# kegboard-mini.net
KiCad netlist of a schematic drawn in EAGLE
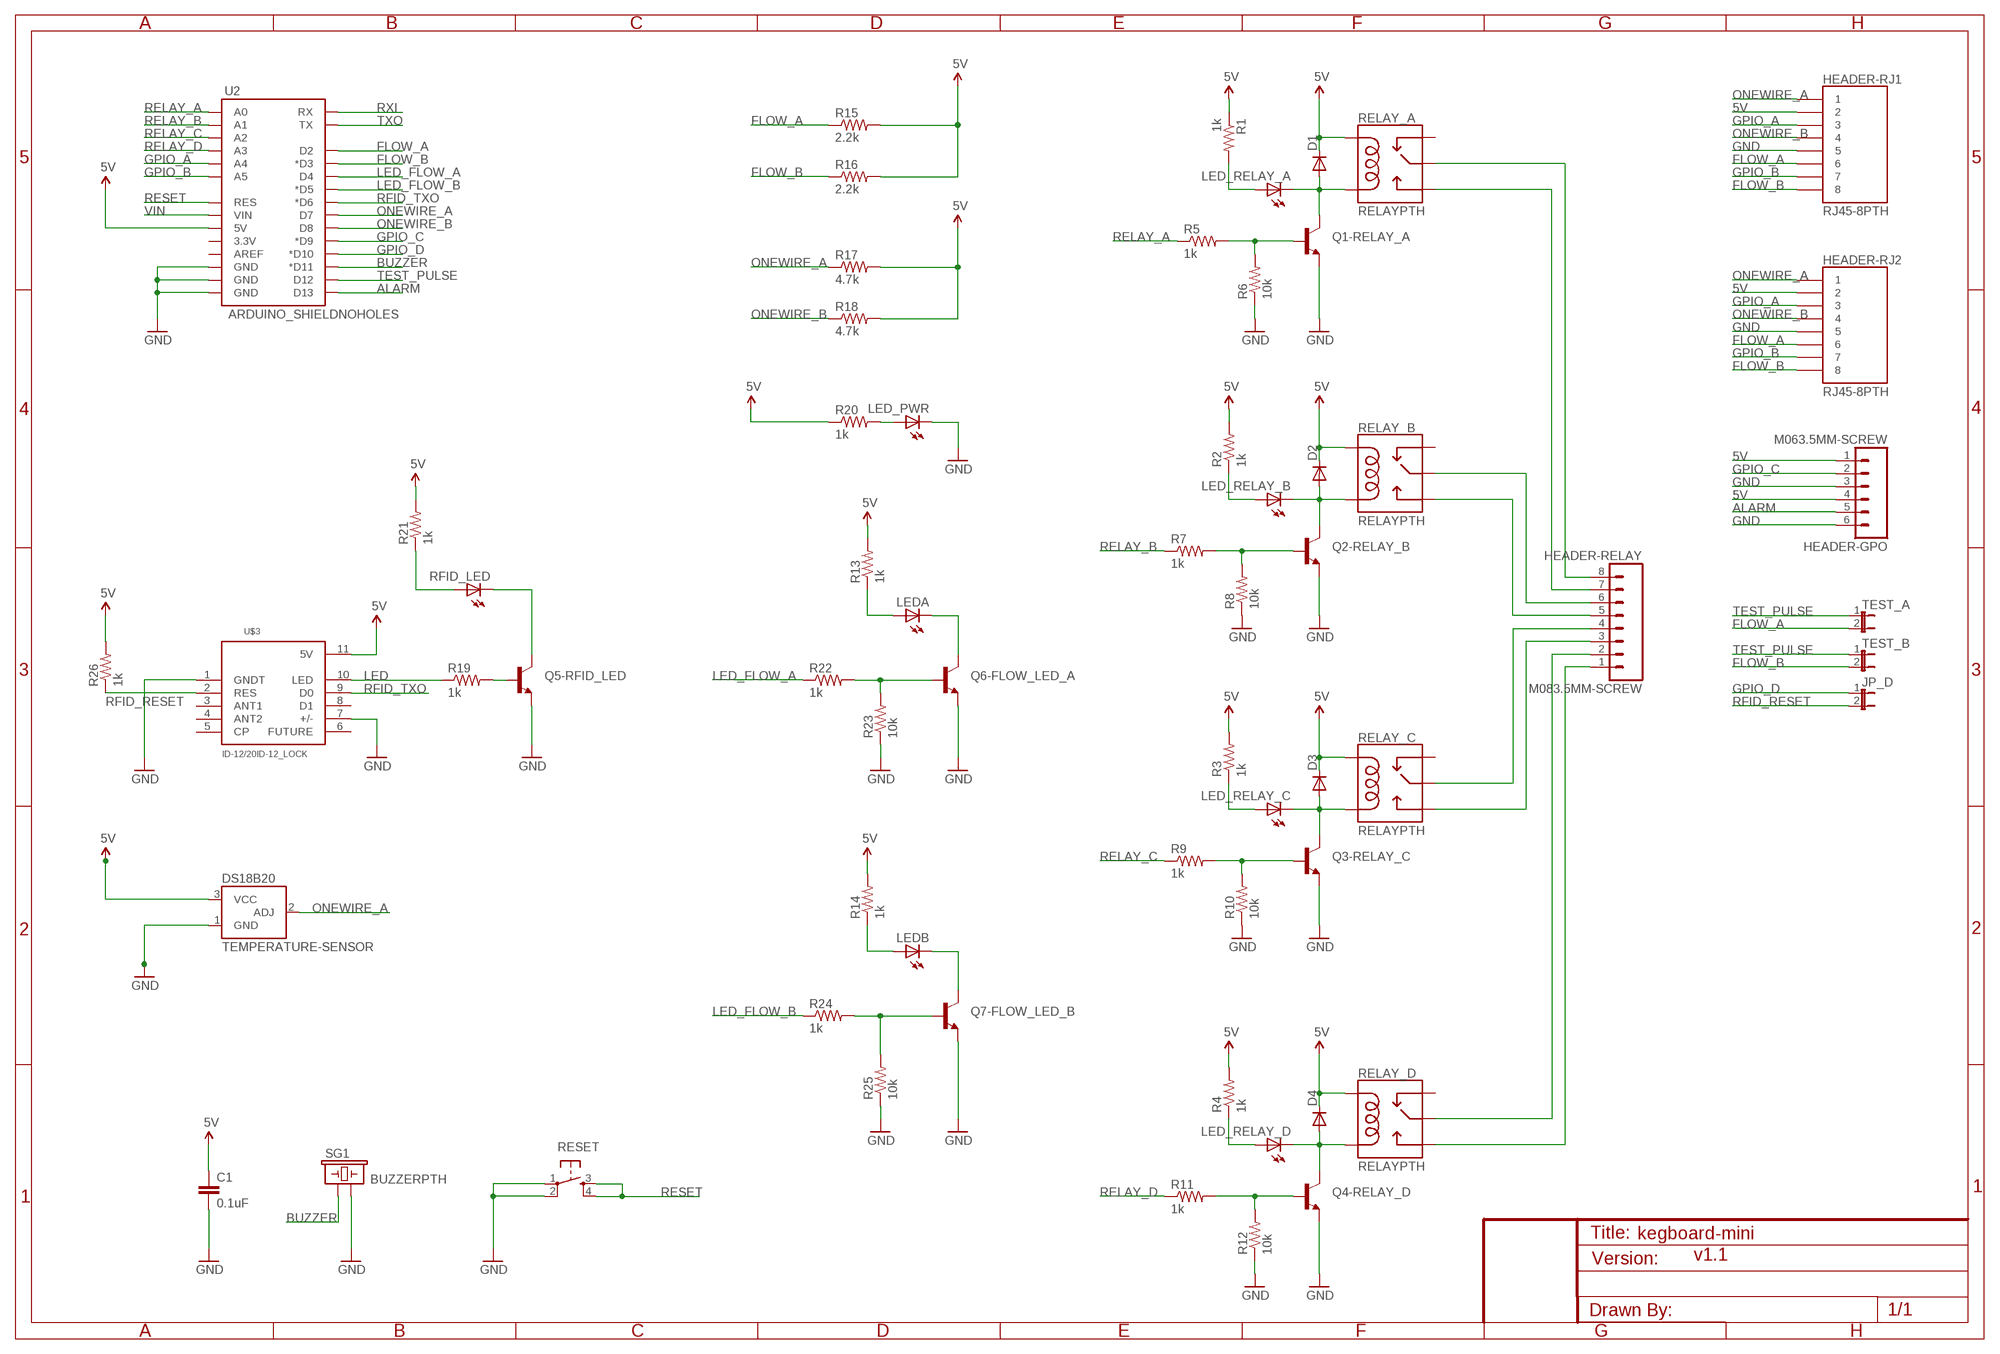
[diagram p0: schematic, sheet 1]

(export (version "E")
  (design (tool "Eeschema 10.0.6"))
  (components
    (comp (ref "C1")
      (value "0.1uF")
      (footprint "eagle-import:CAP-PTH-SMALL")
      (libsource (lib "eagle-import") (part "CAPPTH"))
    )
    (comp (ref "D1")
      (value "DIODE1N4148")
      (footprint "eagle-import:DIODE-1N4148")
      (libsource (lib "eagle-import") (part "DIODE1N4148"))
    )
    (comp (ref "D2")
      (value "DIODE1N4148")
      (footprint "eagle-import:DIODE-1N4148")
      (libsource (lib "eagle-import") (part "DIODE1N4148"))
    )
    (comp (ref "D3")
      (value "DIODE1N4148")
      (footprint "eagle-import:DIODE-1N4148")
      (libsource (lib "eagle-import") (part "DIODE1N4148"))
    )
    (comp (ref "D4")
      (value "DIODE1N4148")
      (footprint "eagle-import:DIODE-1N4148")
      (libsource (lib "eagle-import") (part "DIODE1N4148"))
    )
    (comp (ref "DS18B20")
      (value "TEMPERATURE-SENSOR")
      (footprint "eagle-import:TO-92")
      (libsource (lib "eagle-import") (part "TEMPERATURE-SENSOR"))
    )
    (comp (ref "HEADER-GPO")
      (value "M063.5MM-SCREW")
      (footprint "eagle-import:SCREWTERMINAL-3.5MM-6")
      (libsource (lib "eagle-import") (part "M063.5MM-6"))
    )
    (comp (ref "HEADER-RELAY")
      (value "M083.5MM-SCREW")
      (footprint "eagle-import:SCREWTERMINAL-3.5MM-8")
      (libsource (lib "eagle-import") (part "M083.5MM-8"))
    )
    (comp (ref "HEADER-RJ1")
      (value "RJ45-8PTH")
      (footprint "eagle-import:RJ45-8")
      (libsource (lib "eagle-import") (part "RJ45-8PTH"))
    )
    (comp (ref "HEADER-RJ2")
      (value "RJ45-8PTH")
      (footprint "eagle-import:RJ45-8")
      (libsource (lib "eagle-import") (part "RJ45-8PTH"))
    )
    (comp (ref "JP_D")
      (value "JUMPER-2PTH")
      (footprint "eagle-import:1X02")
      (libsource (lib "eagle-import") (part "JUMPER-2PTH"))
    )
    (comp (ref "LEDA")
      (value "LED3MM")
      (footprint "eagle-import:LED3MM")
      (libsource (lib "eagle-import") (part "LED3MM"))
    )
    (comp (ref "LEDB")
      (value "LED3MM")
      (footprint "eagle-import:LED3MM")
      (libsource (lib "eagle-import") (part "LED3MM"))
    )
    (comp (ref "LED_PWR")
      (value "LED3MM")
      (footprint "eagle-import:LED3MM")
      (libsource (lib "eagle-import") (part "LED3MM"))
    )
    (comp (ref "LED_RELAY_A")
      (value "LED3MM")
      (footprint "eagle-import:LED3MM")
      (libsource (lib "eagle-import") (part "LED3MM"))
    )
    (comp (ref "LED_RELAY_B")
      (value "LED3MM")
      (footprint "eagle-import:LED3MM")
      (libsource (lib "eagle-import") (part "LED3MM"))
    )
    (comp (ref "LED_RELAY_C")
      (value "LED3MM")
      (footprint "eagle-import:LED3MM")
      (libsource (lib "eagle-import") (part "LED3MM"))
    )
    (comp (ref "LED_RELAY_D")
      (value "LED3MM")
      (footprint "eagle-import:LED3MM")
      (libsource (lib "eagle-import") (part "LED3MM"))
    )
    (comp (ref "Q1-RELAY_A")
      (value "TRANSISTOR_NPNTO92")
      (footprint "eagle-import:TO-92")
      (libsource (lib "eagle-import") (part "TRANSISTOR_NPNTO92"))
    )
    (comp (ref "Q2-RELAY_B")
      (value "TRANSISTOR_NPNTO92")
      (footprint "eagle-import:TO-92")
      (libsource (lib "eagle-import") (part "TRANSISTOR_NPNTO92"))
    )
    (comp (ref "Q3-RELAY_C")
      (value "TRANSISTOR_NPNTO92")
      (footprint "eagle-import:TO-92")
      (libsource (lib "eagle-import") (part "TRANSISTOR_NPNTO92"))
    )
    (comp (ref "Q4-RELAY_D")
      (value "TRANSISTOR_NPNTO92")
      (footprint "eagle-import:TO-92")
      (libsource (lib "eagle-import") (part "TRANSISTOR_NPNTO92"))
    )
    (comp (ref "Q5-RFID_LED")
      (value "TRANSISTOR_NPNTO92")
      (footprint "eagle-import:TO-92")
      (libsource (lib "eagle-import") (part "TRANSISTOR_NPNTO92"))
    )
    (comp (ref "Q6-FLOW_LED_A")
      (value "TRANSISTOR_NPNTO92")
      (footprint "eagle-import:TO-92")
      (libsource (lib "eagle-import") (part "TRANSISTOR_NPNTO92"))
    )
    (comp (ref "Q7-FLOW_LED_B")
      (value "TRANSISTOR_NPNTO92")
      (footprint "eagle-import:TO-92")
      (libsource (lib "eagle-import") (part "TRANSISTOR_NPNTO92"))
    )
    (comp (ref "R1")
      (value "1k")
      (footprint "eagle-import:AXIAL-0.3")
      (libsource (lib "eagle-import") (part "RESISTORPTH1"))
    )
    (comp (ref "R2")
      (value "1k")
      (footprint "eagle-import:AXIAL-0.3")
      (libsource (lib "eagle-import") (part "RESISTORPTH1"))
    )
    (comp (ref "R3")
      (value "1k")
      (footprint "eagle-import:AXIAL-0.3")
      (libsource (lib "eagle-import") (part "RESISTORPTH1"))
    )
    (comp (ref "R4")
      (value "1k")
      (footprint "eagle-import:AXIAL-0.3")
      (libsource (lib "eagle-import") (part "RESISTORPTH1"))
    )
    (comp (ref "R5")
      (value "1k")
      (footprint "eagle-import:AXIAL-0.3")
      (libsource (lib "eagle-import") (part "RESISTORPTH1"))
    )
    (comp (ref "R6")
      (value "10k")
      (footprint "eagle-import:AXIAL-0.3")
      (libsource (lib "eagle-import") (part "RESISTORPTH1"))
    )
    (comp (ref "R7")
      (value "1k")
      (footprint "eagle-import:AXIAL-0.3")
      (libsource (lib "eagle-import") (part "RESISTORPTH1"))
    )
    (comp (ref "R8")
      (value "10k")
      (footprint "eagle-import:AXIAL-0.3")
      (libsource (lib "eagle-import") (part "RESISTORPTH1"))
    )
    (comp (ref "R9")
      (value "1k")
      (footprint "eagle-import:AXIAL-0.3")
      (libsource (lib "eagle-import") (part "RESISTORPTH1"))
    )
    (comp (ref "R10")
      (value "10k")
      (footprint "eagle-import:AXIAL-0.3")
      (libsource (lib "eagle-import") (part "RESISTORPTH1"))
    )
    (comp (ref "R11")
      (value "1k")
      (footprint "eagle-import:AXIAL-0.3")
      (libsource (lib "eagle-import") (part "RESISTORPTH1"))
    )
    (comp (ref "R12")
      (value "10k")
      (footprint "eagle-import:AXIAL-0.3")
      (libsource (lib "eagle-import") (part "RESISTORPTH1"))
    )
    (comp (ref "R13")
      (value "1k")
      (footprint "eagle-import:AXIAL-0.3")
      (libsource (lib "eagle-import") (part "RESISTORPTH1"))
    )
    (comp (ref "R14")
      (value "1k")
      (footprint "eagle-import:AXIAL-0.3")
      (libsource (lib "eagle-import") (part "RESISTORPTH1"))
    )
    (comp (ref "R15")
      (value "2.2k")
      (footprint "eagle-import:AXIAL-0.3")
      (libsource (lib "eagle-import") (part "RESISTORPTH1"))
    )
    (comp (ref "R16")
      (value "2.2k")
      (footprint "eagle-import:AXIAL-0.3")
      (libsource (lib "eagle-import") (part "RESISTORPTH1"))
    )
    (comp (ref "R17")
      (value "4.7k")
      (footprint "eagle-import:AXIAL-0.3")
      (libsource (lib "eagle-import") (part "RESISTORPTH1"))
    )
    (comp (ref "R18")
      (value "4.7k")
      (footprint "eagle-import:AXIAL-0.3")
      (libsource (lib "eagle-import") (part "RESISTORPTH1"))
    )
    (comp (ref "R19")
      (value "1k")
      (footprint "eagle-import:AXIAL-0.3")
      (libsource (lib "eagle-import") (part "RESISTORPTH1"))
    )
    (comp (ref "R20")
      (value "1k")
      (footprint "eagle-import:AXIAL-0.3")
      (libsource (lib "eagle-import") (part "RESISTORPTH1"))
    )
    (comp (ref "R21")
      (value "1k")
      (footprint "eagle-import:AXIAL-0.3")
      (libsource (lib "eagle-import") (part "RESISTORPTH1"))
    )
    (comp (ref "R22")
      (value "1k")
      (footprint "eagle-import:AXIAL-0.3")
      (libsource (lib "eagle-import") (part "RESISTORPTH1"))
    )
    (comp (ref "R23")
      (value "10k")
      (footprint "eagle-import:AXIAL-0.3")
      (libsource (lib "eagle-import") (part "RESISTORPTH1"))
    )
    (comp (ref "R24")
      (value "1k")
      (footprint "eagle-import:AXIAL-0.3")
      (libsource (lib "eagle-import") (part "RESISTORPTH1"))
    )
    (comp (ref "R25")
      (value "10k")
      (footprint "eagle-import:AXIAL-0.3")
      (libsource (lib "eagle-import") (part "RESISTORPTH1"))
    )
    (comp (ref "R26")
      (value "1k")
      (footprint "eagle-import:AXIAL-0.3")
      (libsource (lib "eagle-import") (part "RESISTORPTH1"))
    )
    (comp (ref "RELAY_A")
      (value "RELAYPTH")
      (footprint "eagle-import:RELAY-G5Q")
      (libsource (lib "eagle-import") (part "RELAYPTH"))
    )
    (comp (ref "RELAY_B")
      (value "RELAYPTH")
      (footprint "eagle-import:RELAY-G5Q")
      (libsource (lib "eagle-import") (part "RELAYPTH"))
    )
    (comp (ref "RELAY_C")
      (value "RELAYPTH")
      (footprint "eagle-import:RELAY-G5Q")
      (libsource (lib "eagle-import") (part "RELAYPTH"))
    )
    (comp (ref "RELAY_D")
      (value "RELAYPTH")
      (footprint "eagle-import:RELAY-G5Q")
      (libsource (lib "eagle-import") (part "RELAYPTH"))
    )
    (comp (ref "RESET")
      (value "TAC_SWITCHPTH")
      (footprint "eagle-import:TACTILE-PTH")
      (libsource (lib "eagle-import") (part "TAC_SWITCHPTH"))
    )
    (comp (ref "RFID_LED")
      (value "LED3MM")
      (footprint "eagle-import:LED3MM")
      (libsource (lib "eagle-import") (part "LED3MM"))
    )
    (comp (ref "SG1")
      (value "BUZZERPTH")
      (footprint "eagle-import:BUZZER-12MM")
      (libsource (lib "eagle-import") (part "BUZZERPTH"))
    )
    (comp (ref "TEST_A")
      (value "JUMPER-2PTH")
      (footprint "eagle-import:1X02")
      (libsource (lib "eagle-import") (part "JUMPER-2PTH"))
    )
    (comp (ref "TEST_B")
      (value "JUMPER-2PTH")
      (footprint "eagle-import:1X02")
      (libsource (lib "eagle-import") (part "JUMPER-2PTH"))
    )
    (comp (ref "U$3")
      (value "ID-12/20ID-12_LOCK")
      (footprint "eagle-import:ID-12_LOCK")
      (libsource (lib "eagle-import") (part "ID-12/20ID-12_LOCK"))
    )
    (comp (ref "U2")
      (value "ARDUINO_SHIELDNOHOLES")
      (footprint "eagle-import:DUEMILANOVE_SHIELD_NOHOLES")
      (libsource (lib "eagle-import") (part "ARDUINO_SHIELDNOHOLES"))
    )
  )
  (nets
    (net (code "1") (name "/ALARM") (class "Default")
      (node (ref "HEADER-GPO") (pin "5") (pinfunction "5_5") (pintype "passive"))
      (node (ref "U2") (pin "D13") (pinfunction "D13_D13") (pintype "bidirectional"))
    )
    (net (code "2") (name "/BUZZER") (class "Default")
      (node (ref "SG1") (pin "+") (pinfunction "1_+") (pintype "passive"))
      (node (ref "U2") (pin "D11") (pinfunction "*D11_D11") (pintype "bidirectional"))
    )
    (net (code "3") (name "/FLOW_A") (class "Default")
      (node (ref "HEADER-RJ1") (pin "6") (pinfunction "6_6") (pintype "bidirectional"))
      (node (ref "HEADER-RJ2") (pin "6") (pinfunction "6_6") (pintype "bidirectional"))
      (node (ref "R15") (pin "P$1") (pinfunction "1_P$1") (pintype "passive"))
      (node (ref "TEST_A") (pin "2") (pinfunction "2_2") (pintype "passive"))
      (node (ref "U2") (pin "D2") (pinfunction "D2_D2") (pintype "bidirectional"))
    )
    (net (code "4") (name "/FLOW_B") (class "Default")
      (node (ref "HEADER-RJ1") (pin "8") (pinfunction "8_8") (pintype "bidirectional"))
      (node (ref "HEADER-RJ2") (pin "8") (pinfunction "8_8") (pintype "bidirectional"))
      (node (ref "R16") (pin "P$1") (pinfunction "1_P$1") (pintype "passive"))
      (node (ref "TEST_B") (pin "2") (pinfunction "2_2") (pintype "passive"))
      (node (ref "U2") (pin "D3") (pinfunction "*D3_D3") (pintype "bidirectional"))
    )
    (net (code "5") (name "/GPIO_A") (class "Default")
      (node (ref "HEADER-RJ1") (pin "3") (pinfunction "3_3") (pintype "bidirectional"))
      (node (ref "HEADER-RJ2") (pin "3") (pinfunction "3_3") (pintype "bidirectional"))
      (node (ref "U2") (pin "A4") (pinfunction "A4_A4") (pintype "bidirectional"))
    )
    (net (code "6") (name "/GPIO_B") (class "Default")
      (node (ref "HEADER-RJ1") (pin "7") (pinfunction "7_7") (pintype "bidirectional"))
      (node (ref "HEADER-RJ2") (pin "7") (pinfunction "7_7") (pintype "bidirectional"))
      (node (ref "U2") (pin "A5") (pinfunction "A5_A5") (pintype "bidirectional"))
    )
    (net (code "7") (name "/GPIO_C") (class "Default")
      (node (ref "HEADER-GPO") (pin "2") (pinfunction "2_2") (pintype "passive"))
      (node (ref "U2") (pin "D9") (pinfunction "*D9_D9") (pintype "bidirectional"))
    )
    (net (code "8") (name "/GPIO_D") (class "Default")
      (node (ref "JP_D") (pin "1") (pinfunction "1_1") (pintype "passive"))
      (node (ref "U2") (pin "D10") (pinfunction "*D10_D10") (pintype "bidirectional"))
    )
    (net (code "9") (name "/LED") (class "Default")
      (node (ref "R19") (pin "P$1") (pinfunction "1_P$1") (pintype "passive"))
      (node (ref "U$3") (pin "10") (pinfunction "LED_10") (pintype "bidirectional"))
    )
    (net (code "10") (name "/LED_FLOW_A") (class "Default")
      (node (ref "R22") (pin "P$1") (pinfunction "1_P$1") (pintype "passive"))
      (node (ref "U2") (pin "D4") (pinfunction "D4_D4") (pintype "bidirectional"))
    )
    (net (code "11") (name "/LED_FLOW_B") (class "Default")
      (node (ref "R24") (pin "P$1") (pinfunction "1_P$1") (pintype "passive"))
      (node (ref "U2") (pin "D5") (pinfunction "*D5_D5") (pintype "bidirectional"))
    )
    (net (code "12") (name "/ONEWIRE_A") (class "Default")
      (node (ref "DS18B20") (pin "2") (pinfunction "ADJ_2") (pintype "bidirectional"))
      (node (ref "HEADER-RJ1") (pin "1") (pinfunction "1_1") (pintype "bidirectional"))
      (node (ref "HEADER-RJ2") (pin "1") (pinfunction "1_1") (pintype "bidirectional"))
      (node (ref "R17") (pin "P$1") (pinfunction "1_P$1") (pintype "passive"))
      (node (ref "U2") (pin "D7") (pinfunction "D7_D7") (pintype "bidirectional"))
    )
    (net (code "13") (name "/ONEWIRE_B") (class "Default")
      (node (ref "HEADER-RJ1") (pin "4") (pinfunction "4_4") (pintype "bidirectional"))
      (node (ref "HEADER-RJ2") (pin "4") (pinfunction "4_4") (pintype "bidirectional"))
      (node (ref "R18") (pin "P$1") (pinfunction "1_P$1") (pintype "passive"))
      (node (ref "U2") (pin "D8") (pinfunction "D8_D8") (pintype "bidirectional"))
    )
    (net (code "14") (name "/RELAY_A") (class "Default")
      (node (ref "R5") (pin "P$1") (pinfunction "1_P$1") (pintype "passive"))
      (node (ref "U2") (pin "A0") (pinfunction "A0_A0") (pintype "bidirectional"))
    )
    (net (code "15") (name "/RELAY_B") (class "Default")
      (node (ref "R7") (pin "P$1") (pinfunction "1_P$1") (pintype "passive"))
      (node (ref "U2") (pin "A1") (pinfunction "A1_A1") (pintype "bidirectional"))
    )
    (net (code "16") (name "/RELAY_C") (class "Default")
      (node (ref "R9") (pin "P$1") (pinfunction "1_P$1") (pintype "passive"))
      (node (ref "U2") (pin "A2") (pinfunction "A2_A2") (pintype "bidirectional"))
    )
    (net (code "17") (name "/RELAY_D") (class "Default")
      (node (ref "R11") (pin "P$1") (pinfunction "1_P$1") (pintype "passive"))
      (node (ref "U2") (pin "A3") (pinfunction "A3_A3") (pintype "bidirectional"))
    )
    (net (code "18") (name "/RESET") (class "Default")
      (node (ref "RESET") (pin "3") (pinfunction "3_3") (pintype "passive"))
      (node (ref "RESET") (pin "4") (pinfunction "4_4") (pintype "passive"))
      (node (ref "U2") (pin "RES") (pinfunction "RES_RES") (pintype "bidirectional"))
    )
    (net (code "19") (name "/RFID_RESET") (class "Default")
      (node (ref "JP_D") (pin "2") (pinfunction "2_2") (pintype "passive"))
      (node (ref "R26") (pin "P$1") (pinfunction "1_P$1") (pintype "passive"))
      (node (ref "U$3") (pin "2") (pinfunction "RES_2") (pintype "bidirectional"))
    )
    (net (code "20") (name "/RFID_TXO") (class "Default")
      (node (ref "U$3") (pin "9") (pinfunction "D0_9") (pintype "bidirectional"))
      (node (ref "U2") (pin "D6") (pinfunction "*D6_D6") (pintype "bidirectional"))
    )
    (net (code "21") (name "/RXI") (class "Default")
      (node (ref "U2") (pin "RX") (pinfunction "RX_RX") (pintype "bidirectional"))
    )
    (net (code "22") (name "/TEST_PULSE") (class "Default")
      (node (ref "TEST_A") (pin "1") (pinfunction "1_1") (pintype "passive"))
      (node (ref "TEST_B") (pin "1") (pinfunction "1_1") (pintype "passive"))
      (node (ref "U2") (pin "D12") (pinfunction "D12_D12") (pintype "bidirectional"))
    )
    (net (code "23") (name "/TXO") (class "Default")
      (node (ref "U2") (pin "TX") (pinfunction "TX_TX") (pintype "bidirectional"))
    )
    (net (code "24") (name "/VIN") (class "Default")
      (node (ref "U2") (pin "VIN") (pinfunction "VIN_VIN") (pintype "bidirectional"))
    )
    (net (code "25") (name "5V") (class "Default")
      (node (ref "C1") (pin "1") (pinfunction "1_1") (pintype "passive"))
      (node (ref "D1") (pin "C") (pinfunction "C_C") (pintype "passive"))
      (node (ref "D2") (pin "C") (pinfunction "C_C") (pintype "passive"))
      (node (ref "D3") (pin "C") (pinfunction "C_C") (pintype "passive"))
      (node (ref "D4") (pin "C") (pinfunction "C_C") (pintype "passive"))
      (node (ref "DS18B20") (pin "3") (pinfunction "VCC_3") (pintype "bidirectional"))
      (node (ref "HEADER-GPO") (pin "1") (pinfunction "1_1") (pintype "passive"))
      (node (ref "HEADER-GPO") (pin "4") (pinfunction "4_4") (pintype "passive"))
      (node (ref "HEADER-RJ1") (pin "2") (pinfunction "2_2") (pintype "bidirectional"))
      (node (ref "HEADER-RJ2") (pin "2") (pinfunction "2_2") (pintype "bidirectional"))
      (node (ref "R1") (pin "P$1") (pinfunction "1_P$1") (pintype "passive"))
      (node (ref "R13") (pin "P$2") (pinfunction "2_P$2") (pintype "passive"))
      (node (ref "R14") (pin "P$2") (pinfunction "2_P$2") (pintype "passive"))
      (node (ref "R15") (pin "P$2") (pinfunction "2_P$2") (pintype "passive"))
      (node (ref "R16") (pin "P$2") (pinfunction "2_P$2") (pintype "passive"))
      (node (ref "R17") (pin "P$2") (pinfunction "2_P$2") (pintype "passive"))
      (node (ref "R18") (pin "P$2") (pinfunction "2_P$2") (pintype "passive"))
      (node (ref "R2") (pin "P$2") (pinfunction "2_P$2") (pintype "passive"))
      (node (ref "R20") (pin "P$1") (pinfunction "1_P$1") (pintype "passive"))
      (node (ref "R21") (pin "P$2") (pinfunction "2_P$2") (pintype "passive"))
      (node (ref "R26") (pin "P$2") (pinfunction "2_P$2") (pintype "passive"))
      (node (ref "R3") (pin "P$2") (pinfunction "2_P$2") (pintype "passive"))
      (node (ref "R4") (pin "P$2") (pinfunction "2_P$2") (pintype "passive"))
      (node (ref "RELAY_A") (pin "5") (pinfunction "COIL1_5") (pintype "bidirectional"))
      (node (ref "RELAY_B") (pin "5") (pinfunction "COIL1_5") (pintype "bidirectional"))
      (node (ref "RELAY_C") (pin "5") (pinfunction "COIL1_5") (pintype "bidirectional"))
      (node (ref "RELAY_D") (pin "5") (pinfunction "COIL1_5") (pintype "bidirectional"))
      (node (ref "U$3") (pin "11") (pinfunction "5V_11") (pintype "bidirectional"))
      (node (ref "U2") (pin "5V") (pinfunction "5V_5V") (pintype "bidirectional"))
    )
    (net (code "26") (name "GND") (class "Default")
      (node (ref "C1") (pin "2") (pinfunction "2_2") (pintype "passive"))
      (node (ref "DS18B20") (pin "1") (pinfunction "GND_1") (pintype "bidirectional"))
      (node (ref "HEADER-GPO") (pin "3") (pinfunction "3_3") (pintype "passive"))
      (node (ref "HEADER-GPO") (pin "6") (pinfunction "6_6") (pintype "passive"))
      (node (ref "HEADER-RJ1") (pin "5") (pinfunction "5_5") (pintype "bidirectional"))
      (node (ref "HEADER-RJ2") (pin "5") (pinfunction "5_5") (pintype "bidirectional"))
      (node (ref "LED_PWR") (pin "K") (pinfunction "C_K") (pintype "passive"))
      (node (ref "Q1-RELAY_A") (pin "1") (pinfunction "E_1") (pintype "passive"))
      (node (ref "Q2-RELAY_B") (pin "1") (pinfunction "E_1") (pintype "passive"))
      (node (ref "Q3-RELAY_C") (pin "1") (pinfunction "E_1") (pintype "passive"))
      (node (ref "Q4-RELAY_D") (pin "1") (pinfunction "E_1") (pintype "passive"))
      (node (ref "Q5-RFID_LED") (pin "1") (pinfunction "E_1") (pintype "passive"))
      (node (ref "Q6-FLOW_LED_A") (pin "1") (pinfunction "E_1") (pintype "passive"))
      (node (ref "Q7-FLOW_LED_B") (pin "1") (pinfunction "E_1") (pintype "passive"))
      (node (ref "R10") (pin "P$1") (pinfunction "1_P$1") (pintype "passive"))
      (node (ref "R12") (pin "P$1") (pinfunction "1_P$1") (pintype "passive"))
      (node (ref "R23") (pin "P$1") (pinfunction "1_P$1") (pintype "passive"))
      (node (ref "R25") (pin "P$1") (pinfunction "1_P$1") (pintype "passive"))
      (node (ref "R6") (pin "P$1") (pinfunction "1_P$1") (pintype "passive"))
      (node (ref "R8") (pin "P$1") (pinfunction "1_P$1") (pintype "passive"))
      (node (ref "RESET") (pin "1") (pinfunction "1_1") (pintype "passive"))
      (node (ref "RESET") (pin "2") (pinfunction "2_2") (pintype "passive"))
      (node (ref "SG1") (pin "-") (pinfunction "2_-") (pintype "passive"))
      (node (ref "U$3") (pin "1") (pinfunction "GNDT_1") (pintype "bidirectional"))
      (node (ref "U$3") (pin "7") (pinfunction "+/-_7") (pintype "bidirectional"))
      (node (ref "U2") (pin "GND@0") (pinfunction "GND_GND@0") (pintype "bidirectional"))
      (node (ref "U2") (pin "GND@1") (pinfunction "GND_GND@1") (pintype "bidirectional"))
      (node (ref "U2") (pin "GND@2") (pinfunction "GND_GND@2") (pintype "bidirectional"))
    )
    (net (code "27") (name "Net-(LEDA-C)") (class "Default")
      (node (ref "LEDA") (pin "K") (pinfunction "C_K") (pintype "passive"))
      (node (ref "Q6-FLOW_LED_A") (pin "3") (pinfunction "C_3") (pintype "passive"))
    )
    (net (code "28") (name "Net-(LEDB-C)") (class "Default")
      (node (ref "LEDB") (pin "K") (pinfunction "C_K") (pintype "passive"))
      (node (ref "Q7-FLOW_LED_B") (pin "3") (pinfunction "C_3") (pintype "passive"))
    )
    (net (code "29") (name "Net-(LED_RELAY_A-C)") (class "Default")
      (node (ref "D1") (pin "A") (pinfunction "A_A") (pintype "passive"))
      (node (ref "LED_RELAY_A") (pin "K") (pinfunction "C_K") (pintype "passive"))
      (node (ref "Q1-RELAY_A") (pin "3") (pinfunction "C_3") (pintype "passive"))
      (node (ref "RELAY_A") (pin "1") (pinfunction "COIL2_1") (pintype "bidirectional"))
    )
    (net (code "30") (name "Net-(LED_RELAY_B-C)") (class "Default")
      (node (ref "D2") (pin "A") (pinfunction "A_A") (pintype "passive"))
      (node (ref "LED_RELAY_B") (pin "K") (pinfunction "C_K") (pintype "passive"))
      (node (ref "Q2-RELAY_B") (pin "3") (pinfunction "C_3") (pintype "passive"))
      (node (ref "RELAY_B") (pin "1") (pinfunction "COIL2_1") (pintype "bidirectional"))
    )
    (net (code "31") (name "Net-(LED_RELAY_C-C)") (class "Default")
      (node (ref "D3") (pin "A") (pinfunction "A_A") (pintype "passive"))
      (node (ref "LED_RELAY_C") (pin "K") (pinfunction "C_K") (pintype "passive"))
      (node (ref "Q3-RELAY_C") (pin "3") (pinfunction "C_3") (pintype "passive"))
      (node (ref "RELAY_C") (pin "1") (pinfunction "COIL2_1") (pintype "bidirectional"))
    )
    (net (code "32") (name "Net-(LED_RELAY_D-C)") (class "Default")
      (node (ref "D4") (pin "A") (pinfunction "A_A") (pintype "passive"))
      (node (ref "LED_RELAY_D") (pin "K") (pinfunction "C_K") (pintype "passive"))
      (node (ref "Q4-RELAY_D") (pin "3") (pinfunction "C_3") (pintype "passive"))
      (node (ref "RELAY_D") (pin "1") (pinfunction "COIL2_1") (pintype "bidirectional"))
    )
    (net (code "33") (name "Net-(Q1-RELAY_A-B)") (class "Default")
      (node (ref "Q1-RELAY_A") (pin "2") (pinfunction "B_2") (pintype "passive"))
      (node (ref "R5") (pin "P$2") (pinfunction "2_P$2") (pintype "passive"))
      (node (ref "R6") (pin "P$2") (pinfunction "2_P$2") (pintype "passive"))
    )
    (net (code "34") (name "Net-(Q2-RELAY_B-B)") (class "Default")
      (node (ref "Q2-RELAY_B") (pin "2") (pinfunction "B_2") (pintype "passive"))
      (node (ref "R7") (pin "P$2") (pinfunction "2_P$2") (pintype "passive"))
      (node (ref "R8") (pin "P$2") (pinfunction "2_P$2") (pintype "passive"))
    )
    (net (code "35") (name "Net-(Q3-RELAY_C-B)") (class "Default")
      (node (ref "Q3-RELAY_C") (pin "2") (pinfunction "B_2") (pintype "passive"))
      (node (ref "R10") (pin "P$2") (pinfunction "2_P$2") (pintype "passive"))
      (node (ref "R9") (pin "P$2") (pinfunction "2_P$2") (pintype "passive"))
    )
    (net (code "36") (name "Net-(Q4-RELAY_D-B)") (class "Default")
      (node (ref "Q4-RELAY_D") (pin "2") (pinfunction "B_2") (pintype "passive"))
      (node (ref "R11") (pin "P$2") (pinfunction "2_P$2") (pintype "passive"))
      (node (ref "R12") (pin "P$2") (pinfunction "2_P$2") (pintype "passive"))
    )
    (net (code "37") (name "Net-(Q5-RFID_LED-B)") (class "Default")
      (node (ref "Q5-RFID_LED") (pin "2") (pinfunction "B_2") (pintype "passive"))
      (node (ref "R19") (pin "P$2") (pinfunction "2_P$2") (pintype "passive"))
    )
    (net (code "38") (name "Net-(Q5-RFID_LED-C)") (class "Default")
      (node (ref "Q5-RFID_LED") (pin "3") (pinfunction "C_3") (pintype "passive"))
      (node (ref "RFID_LED") (pin "K") (pinfunction "C_K") (pintype "passive"))
    )
    (net (code "39") (name "Net-(Q6-FLOW_LED_A-B)") (class "Default")
      (node (ref "Q6-FLOW_LED_A") (pin "2") (pinfunction "B_2") (pintype "passive"))
      (node (ref "R22") (pin "P$2") (pinfunction "2_P$2") (pintype "passive"))
      (node (ref "R23") (pin "P$2") (pinfunction "2_P$2") (pintype "passive"))
    )
    (net (code "40") (name "Net-(Q7-FLOW_LED_B-B)") (class "Default")
      (node (ref "Q7-FLOW_LED_B") (pin "2") (pinfunction "B_2") (pintype "passive"))
      (node (ref "R24") (pin "P$2") (pinfunction "2_P$2") (pintype "passive"))
      (node (ref "R25") (pin "P$2") (pinfunction "2_P$2") (pintype "passive"))
    )
    (net (code "41") (name "Net-(R1-2)") (class "Default")
      (node (ref "LED_RELAY_A") (pin "A") (pinfunction "A_A") (pintype "passive"))
      (node (ref "R1") (pin "P$2") (pinfunction "2_P$2") (pintype "passive"))
    )
    (net (code "42") (name "Net-(R2-1)") (class "Default")
      (node (ref "LED_RELAY_B") (pin "A") (pinfunction "A_A") (pintype "passive"))
      (node (ref "R2") (pin "P$1") (pinfunction "1_P$1") (pintype "passive"))
    )
    (net (code "43") (name "Net-(R3-1)") (class "Default")
      (node (ref "LED_RELAY_C") (pin "A") (pinfunction "A_A") (pintype "passive"))
      (node (ref "R3") (pin "P$1") (pinfunction "1_P$1") (pintype "passive"))
    )
    (net (code "44") (name "Net-(R4-1)") (class "Default")
      (node (ref "LED_RELAY_D") (pin "A") (pinfunction "A_A") (pintype "passive"))
      (node (ref "R4") (pin "P$1") (pinfunction "1_P$1") (pintype "passive"))
    )
    (net (code "45") (name "Net-(R13-1)") (class "Default")
      (node (ref "LEDA") (pin "A") (pinfunction "A_A") (pintype "passive"))
      (node (ref "R13") (pin "P$1") (pinfunction "1_P$1") (pintype "passive"))
    )
    (net (code "46") (name "Net-(R14-1)") (class "Default")
      (node (ref "LEDB") (pin "A") (pinfunction "A_A") (pintype "passive"))
      (node (ref "R14") (pin "P$1") (pinfunction "1_P$1") (pintype "passive"))
    )
    (net (code "47") (name "Net-(R20-2)") (class "Default")
      (node (ref "LED_PWR") (pin "A") (pinfunction "A_A") (pintype "passive"))
      (node (ref "R20") (pin "P$2") (pinfunction "2_P$2") (pintype "passive"))
    )
    (net (code "48") (name "Net-(R21-1)") (class "Default")
      (node (ref "R21") (pin "P$1") (pinfunction "1_P$1") (pintype "passive"))
      (node (ref "RFID_LED") (pin "A") (pinfunction "A_A") (pintype "passive"))
    )
    (net (code "49") (name "Net-(RELAY_A-MAIN)") (class "Default")
      (node (ref "HEADER-RELAY") (pin "8") (pinfunction "8_8") (pintype "passive"))
      (node (ref "RELAY_A") (pin "2") (pinfunction "MAIN_2") (pintype "bidirectional"))
    )
    (net (code "50") (name "Net-(RELAY_A-NO)") (class "Default")
      (node (ref "HEADER-RELAY") (pin "7") (pinfunction "7_7") (pintype "passive"))
      (node (ref "RELAY_A") (pin "3") (pinfunction "NO_3") (pintype "bidirectional"))
    )
    (net (code "51") (name "Net-(RELAY_B-MAIN)") (class "Default")
      (node (ref "HEADER-RELAY") (pin "6") (pinfunction "6_6") (pintype "passive"))
      (node (ref "RELAY_B") (pin "2") (pinfunction "MAIN_2") (pintype "bidirectional"))
    )
    (net (code "52") (name "Net-(RELAY_B-NO)") (class "Default")
      (node (ref "HEADER-RELAY") (pin "5") (pinfunction "5_5") (pintype "passive"))
      (node (ref "RELAY_B") (pin "3") (pinfunction "NO_3") (pintype "bidirectional"))
    )
    (net (code "53") (name "Net-(RELAY_C-MAIN)") (class "Default")
      (node (ref "HEADER-RELAY") (pin "4") (pinfunction "4_4") (pintype "passive"))
      (node (ref "RELAY_C") (pin "2") (pinfunction "MAIN_2") (pintype "bidirectional"))
    )
    (net (code "54") (name "Net-(RELAY_C-NO)") (class "Default")
      (node (ref "HEADER-RELAY") (pin "3") (pinfunction "3_3") (pintype "passive"))
      (node (ref "RELAY_C") (pin "3") (pinfunction "NO_3") (pintype "bidirectional"))
    )
    (net (code "55") (name "Net-(RELAY_D-MAIN)") (class "Default")
      (node (ref "HEADER-RELAY") (pin "2") (pinfunction "2_2") (pintype "passive"))
      (node (ref "RELAY_D") (pin "2") (pinfunction "MAIN_2") (pintype "bidirectional"))
    )
    (net (code "56") (name "Net-(RELAY_D-NO)") (class "Default")
      (node (ref "HEADER-RELAY") (pin "1") (pinfunction "1_1") (pintype "passive"))
      (node (ref "RELAY_D") (pin "3") (pinfunction "NO_3") (pintype "bidirectional"))
    )
    (net (code "57") (name "unconnected-(RELAY_A-NC-Pad4)") (class "Default")
      (node (ref "RELAY_A") (pin "4") (pinfunction "NC_4") (pintype "bidirectional"))
    )
    (net (code "58") (name "unconnected-(RELAY_B-NC-Pad4)") (class "Default")
      (node (ref "RELAY_B") (pin "4") (pinfunction "NC_4") (pintype "bidirectional"))
    )
    (net (code "59") (name "unconnected-(RELAY_C-NC-Pad4)") (class "Default")
      (node (ref "RELAY_C") (pin "4") (pinfunction "NC_4") (pintype "bidirectional"))
    )
    (net (code "60") (name "unconnected-(RELAY_D-NC-Pad4)") (class "Default")
      (node (ref "RELAY_D") (pin "4") (pinfunction "NC_4") (pintype "bidirectional"))
    )
    (net (code "61") (name "unconnected-(U$3-ANT1-Pad3)") (class "Default")
      (node (ref "U$3") (pin "3") (pinfunction "ANT1_3") (pintype "bidirectional"))
    )
    (net (code "62") (name "unconnected-(U$3-ANT2-Pad4)") (class "Default")
      (node (ref "U$3") (pin "4") (pinfunction "ANT2_4") (pintype "bidirectional"))
    )
    (net (code "63") (name "unconnected-(U$3-CP-Pad5)") (class "Default")
      (node (ref "U$3") (pin "5") (pinfunction "CP_5") (pintype "bidirectional"))
    )
    (net (code "64") (name "unconnected-(U$3-D1-Pad8)") (class "Default")
      (node (ref "U$3") (pin "8") (pinfunction "D1_8") (pintype "bidirectional"))
    )
    (net (code "65") (name "unconnected-(U$3-FUTURE-Pad6)") (class "Default")
      (node (ref "U$3") (pin "6") (pinfunction "FUTURE_6") (pintype "bidirectional"))
    )
    (net (code "66") (name "unconnected-(U2-Pad3.3V)") (class "Default")
      (node (ref "U2") (pin "3.3V") (pinfunction "3.3V_3.3V") (pintype "bidirectional"))
    )
    (net (code "67") (name "unconnected-(U2-PadAREF)") (class "Default")
      (node (ref "U2") (pin "AREF") (pinfunction "AREF_AREF") (pintype "bidirectional"))
    )
  )
)
